# FPGA1_POWER.net
KiCad netlist of a schematic drawn in Altium Designer
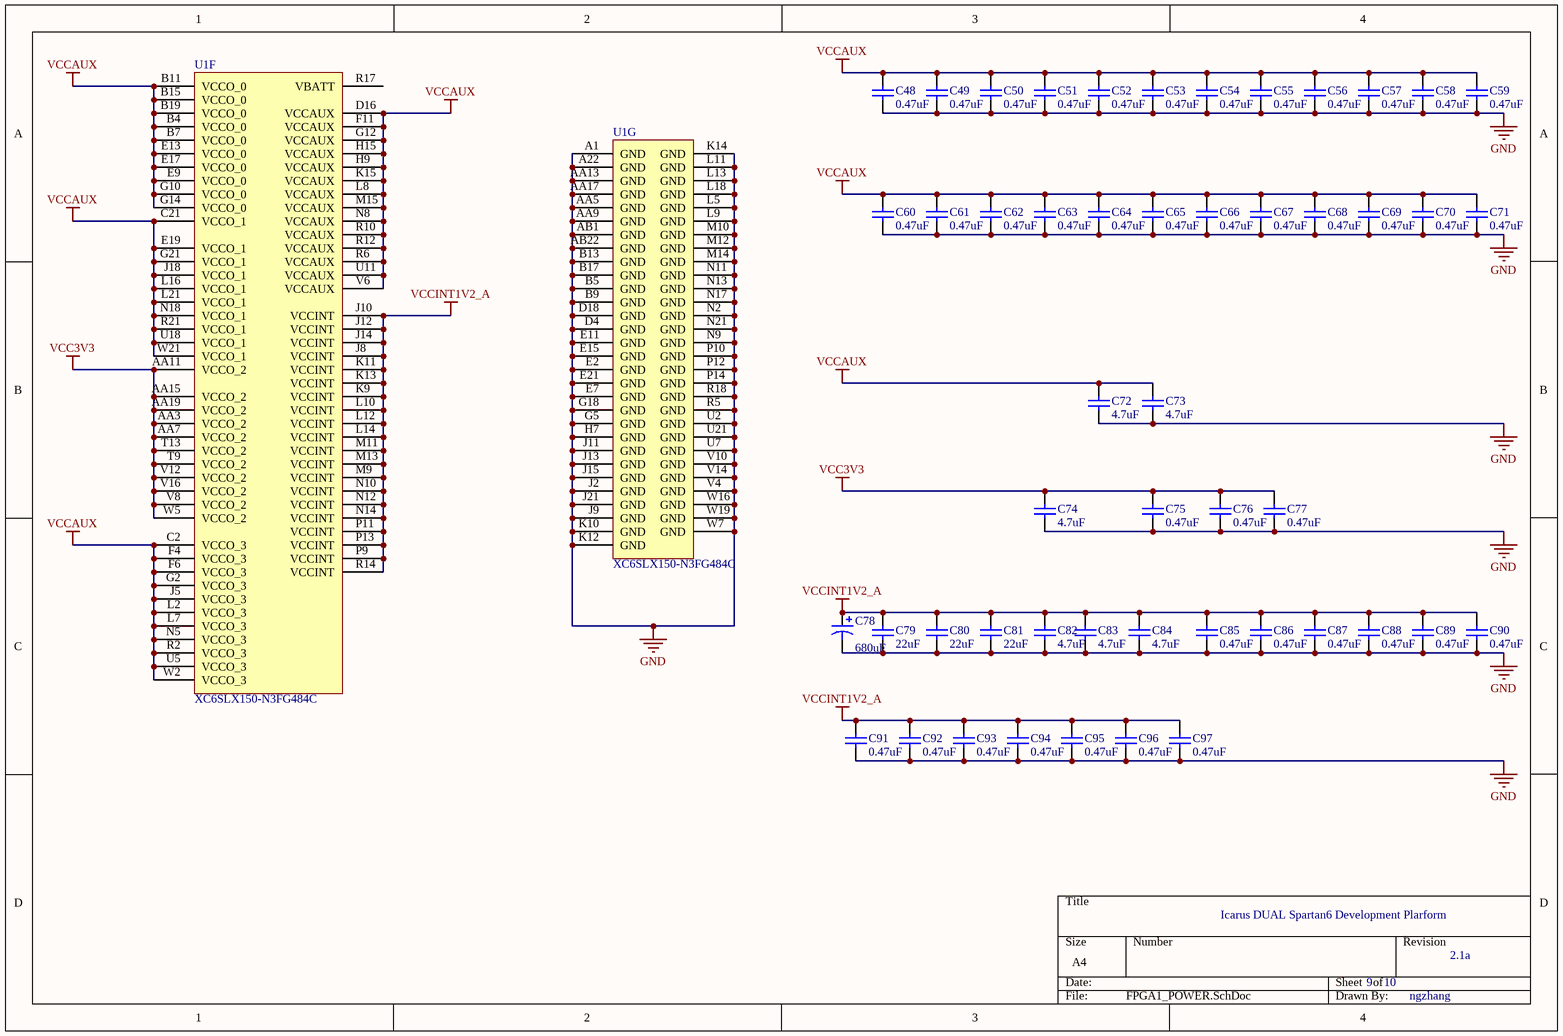
[diagram p0: FPGA1_POWER.SchDoc]

(export (version "E")
  (design (tool "Eeschema 10.0.6"))
  (components
    (comp (ref "C48")
      (value "0.47uF")
      (footprint "0402")
      (description "Capacitor (Semiconductor SIM Model)")
      (fields (field (name "PUBLISHER") "Altium Limited"))
      (libsource (lib "Miscellaneous Devices") (part "Cap Semi"))
    )
    (comp (ref "C49")
      (value "0.47uF")
      (footprint "0402")
      (description "Capacitor (Semiconductor SIM Model)")
      (fields (field (name "PUBLISHER") "Altium Limited"))
      (libsource (lib "Miscellaneous Devices") (part "Cap Semi"))
    )
    (comp (ref "C50")
      (value "0.47uF")
      (footprint "0402")
      (description "Capacitor (Semiconductor SIM Model)")
      (fields (field (name "PUBLISHER") "Altium Limited"))
      (libsource (lib "Miscellaneous Devices") (part "Cap Semi"))
    )
    (comp (ref "C51")
      (value "0.47uF")
      (footprint "0402")
      (description "Capacitor (Semiconductor SIM Model)")
      (fields (field (name "PUBLISHER") "Altium Limited"))
      (libsource (lib "Miscellaneous Devices") (part "Cap Semi"))
    )
    (comp (ref "C52")
      (value "0.47uF")
      (footprint "0402")
      (description "Capacitor (Semiconductor SIM Model)")
      (fields (field (name "PUBLISHER") "Altium Limited"))
      (libsource (lib "Miscellaneous Devices") (part "Cap Semi"))
    )
    (comp (ref "C53")
      (value "0.47uF")
      (footprint "0402")
      (description "Capacitor (Semiconductor SIM Model)")
      (fields (field (name "PUBLISHER") "Altium Limited"))
      (libsource (lib "Miscellaneous Devices") (part "Cap Semi"))
    )
    (comp (ref "C54")
      (value "0.47uF")
      (footprint "0402")
      (description "Capacitor (Semiconductor SIM Model)")
      (fields (field (name "PUBLISHER") "Altium Limited"))
      (libsource (lib "Miscellaneous Devices") (part "Cap Semi"))
    )
    (comp (ref "C55")
      (value "0.47uF")
      (footprint "0402")
      (description "Capacitor (Semiconductor SIM Model)")
      (fields (field (name "PUBLISHER") "Altium Limited"))
      (libsource (lib "Miscellaneous Devices") (part "Cap Semi"))
    )
    (comp (ref "C56")
      (value "0.47uF")
      (footprint "0402")
      (description "Capacitor (Semiconductor SIM Model)")
      (fields (field (name "PUBLISHER") "Altium Limited"))
      (libsource (lib "Miscellaneous Devices") (part "Cap Semi"))
    )
    (comp (ref "C57")
      (value "0.47uF")
      (footprint "0402")
      (description "Capacitor (Semiconductor SIM Model)")
      (fields (field (name "PUBLISHER") "Altium Limited"))
      (libsource (lib "Miscellaneous Devices") (part "Cap Semi"))
    )
    (comp (ref "C58")
      (value "0.47uF")
      (footprint "0402")
      (description "Capacitor (Semiconductor SIM Model)")
      (fields (field (name "PUBLISHER") "Altium Limited"))
      (libsource (lib "Miscellaneous Devices") (part "Cap Semi"))
    )
    (comp (ref "C59")
      (value "0.47uF")
      (footprint "0402")
      (description "Capacitor (Semiconductor SIM Model)")
      (fields (field (name "PUBLISHER") "Altium Limited"))
      (libsource (lib "Miscellaneous Devices") (part "Cap Semi"))
    )
    (comp (ref "C60")
      (value "0.47uF")
      (footprint "0402")
      (description "Capacitor (Semiconductor SIM Model)")
      (fields (field (name "PUBLISHER") "Altium Limited"))
      (libsource (lib "Miscellaneous Devices") (part "Cap Semi"))
    )
    (comp (ref "C61")
      (value "0.47uF")
      (footprint "0402")
      (description "Capacitor (Semiconductor SIM Model)")
      (fields (field (name "PUBLISHER") "Altium Limited"))
      (libsource (lib "Miscellaneous Devices") (part "Cap Semi"))
    )
    (comp (ref "C62")
      (value "0.47uF")
      (footprint "0402")
      (description "Capacitor (Semiconductor SIM Model)")
      (fields (field (name "PUBLISHER") "Altium Limited"))
      (libsource (lib "Miscellaneous Devices") (part "Cap Semi"))
    )
    (comp (ref "C63")
      (value "0.47uF")
      (footprint "0402")
      (description "Capacitor (Semiconductor SIM Model)")
      (fields (field (name "PUBLISHER") "Altium Limited"))
      (libsource (lib "Miscellaneous Devices") (part "Cap Semi"))
    )
    (comp (ref "C64")
      (value "0.47uF")
      (footprint "0402")
      (description "Capacitor (Semiconductor SIM Model)")
      (fields (field (name "PUBLISHER") "Altium Limited"))
      (libsource (lib "Miscellaneous Devices") (part "Cap Semi"))
    )
    (comp (ref "C65")
      (value "0.47uF")
      (footprint "0402")
      (description "Capacitor (Semiconductor SIM Model)")
      (fields (field (name "PUBLISHER") "Altium Limited"))
      (libsource (lib "Miscellaneous Devices") (part "Cap Semi"))
    )
    (comp (ref "C66")
      (value "0.47uF")
      (footprint "0402")
      (description "Capacitor (Semiconductor SIM Model)")
      (fields (field (name "PUBLISHER") "Altium Limited"))
      (libsource (lib "Miscellaneous Devices") (part "Cap Semi"))
    )
    (comp (ref "C67")
      (value "0.47uF")
      (footprint "0402")
      (description "Capacitor (Semiconductor SIM Model)")
      (fields (field (name "PUBLISHER") "Altium Limited"))
      (libsource (lib "Miscellaneous Devices") (part "Cap Semi"))
    )
    (comp (ref "C68")
      (value "0.47uF")
      (footprint "0402")
      (description "Capacitor (Semiconductor SIM Model)")
      (fields (field (name "PUBLISHER") "Altium Limited"))
      (libsource (lib "Miscellaneous Devices") (part "Cap Semi"))
    )
    (comp (ref "C69")
      (value "0.47uF")
      (footprint "0402")
      (description "Capacitor (Semiconductor SIM Model)")
      (fields (field (name "PUBLISHER") "Altium Limited"))
      (libsource (lib "Miscellaneous Devices") (part "Cap Semi"))
    )
    (comp (ref "C70")
      (value "0.47uF")
      (footprint "0402")
      (description "Capacitor (Semiconductor SIM Model)")
      (fields (field (name "PUBLISHER") "Altium Limited"))
      (libsource (lib "Miscellaneous Devices") (part "Cap Semi"))
    )
    (comp (ref "C71")
      (value "0.47uF")
      (footprint "0402")
      (description "Capacitor (Semiconductor SIM Model)")
      (fields (field (name "PUBLISHER") "Altium Limited"))
      (libsource (lib "Miscellaneous Devices") (part "Cap Semi"))
    )
    (comp (ref "C72")
      (value "4.7uF")
      (footprint "C0805")
      (description "Capacitor (Semiconductor SIM Model)")
      (fields (field (name "PUBLISHER") "Altium Limited"))
      (libsource (lib "Miscellaneous Devices") (part "Cap Semi"))
    )
    (comp (ref "C73")
      (value "4.7uF")
      (footprint "C0805")
      (description "Capacitor (Semiconductor SIM Model)")
      (fields (field (name "PUBLISHER") "Altium Limited"))
      (libsource (lib "Miscellaneous Devices") (part "Cap Semi"))
    )
    (comp (ref "C74")
      (value "4.7uF")
      (footprint "C0805")
      (description "Capacitor (Semiconductor SIM Model)")
      (fields (field (name "PUBLISHER") "Altium Limited"))
      (libsource (lib "Miscellaneous Devices") (part "Cap Semi"))
    )
    (comp (ref "C75")
      (value "0.47uF")
      (footprint "0402")
      (description "Capacitor (Semiconductor SIM Model)")
      (fields (field (name "PUBLISHER") "Altium Limited"))
      (libsource (lib "Miscellaneous Devices") (part "Cap Semi"))
    )
    (comp (ref "C76")
      (value "0.47uF")
      (footprint "0402")
      (description "Capacitor (Semiconductor SIM Model)")
      (fields (field (name "PUBLISHER") "Altium Limited"))
      (libsource (lib "Miscellaneous Devices") (part "Cap Semi"))
    )
    (comp (ref "C77")
      (value "0.47uF")
      (footprint "0402")
      (description "Capacitor (Semiconductor SIM Model)")
      (fields (field (name "PUBLISHER") "Altium Limited"))
      (libsource (lib "Miscellaneous Devices") (part "Cap Semi"))
    )
    (comp (ref "C78")
      (value "680uF")
      (footprint "D")
      (description "Polarized Capacitor (Surface Mount)")
      (fields (field (name "PUBLISHER") "Altium Limited"))
      (libsource (lib "Miscellaneous Devices") (part "Cap Pol3"))
    )
    (comp (ref "C79")
      (value "22uF")
      (footprint "C1206")
      (description "Capacitor (Semiconductor SIM Model)")
      (fields (field (name "PUBLISHER") "Altium Limited"))
      (libsource (lib "Miscellaneous Devices") (part "Cap Semi"))
    )
    (comp (ref "C80")
      (value "22uF")
      (footprint "C1206")
      (description "Capacitor (Semiconductor SIM Model)")
      (fields (field (name "PUBLISHER") "Altium Limited"))
      (libsource (lib "Miscellaneous Devices") (part "Cap Semi"))
    )
    (comp (ref "C81")
      (value "22uF")
      (footprint "C1206")
      (description "Capacitor (Semiconductor SIM Model)")
      (fields (field (name "PUBLISHER") "Altium Limited"))
      (libsource (lib "Miscellaneous Devices") (part "Cap Semi"))
    )
    (comp (ref "C82")
      (value "4.7uF")
      (footprint "C0805")
      (description "Capacitor (Semiconductor SIM Model)")
      (fields (field (name "PUBLISHER") "Altium Limited"))
      (libsource (lib "Miscellaneous Devices") (part "Cap Semi"))
    )
    (comp (ref "C83")
      (value "4.7uF")
      (footprint "C0805")
      (description "Capacitor (Semiconductor SIM Model)")
      (fields (field (name "PUBLISHER") "Altium Limited"))
      (libsource (lib "Miscellaneous Devices") (part "Cap Semi"))
    )
    (comp (ref "C84")
      (value "4.7uF")
      (footprint "C0805")
      (description "Capacitor (Semiconductor SIM Model)")
      (fields (field (name "PUBLISHER") "Altium Limited"))
      (libsource (lib "Miscellaneous Devices") (part "Cap Semi"))
    )
    (comp (ref "C85")
      (value "0.47uF")
      (footprint "0402")
      (description "Capacitor (Semiconductor SIM Model)")
      (fields (field (name "PUBLISHER") "Altium Limited"))
      (libsource (lib "Miscellaneous Devices") (part "Cap Semi"))
    )
    (comp (ref "C86")
      (value "0.47uF")
      (footprint "0402")
      (description "Capacitor (Semiconductor SIM Model)")
      (fields (field (name "PUBLISHER") "Altium Limited"))
      (libsource (lib "Miscellaneous Devices") (part "Cap Semi"))
    )
    (comp (ref "C87")
      (value "0.47uF")
      (footprint "0402")
      (description "Capacitor (Semiconductor SIM Model)")
      (fields (field (name "PUBLISHER") "Altium Limited"))
      (libsource (lib "Miscellaneous Devices") (part "Cap Semi"))
    )
    (comp (ref "C88")
      (value "0.47uF")
      (footprint "0402")
      (description "Capacitor (Semiconductor SIM Model)")
      (fields (field (name "PUBLISHER") "Altium Limited"))
      (libsource (lib "Miscellaneous Devices") (part "Cap Semi"))
    )
    (comp (ref "C89")
      (value "0.47uF")
      (footprint "0402")
      (description "Capacitor (Semiconductor SIM Model)")
      (fields (field (name "PUBLISHER") "Altium Limited"))
      (libsource (lib "Miscellaneous Devices") (part "Cap Semi"))
    )
    (comp (ref "C90")
      (value "0.47uF")
      (footprint "0402")
      (description "Capacitor (Semiconductor SIM Model)")
      (fields (field (name "PUBLISHER") "Altium Limited"))
      (libsource (lib "Miscellaneous Devices") (part "Cap Semi"))
    )
    (comp (ref "C91")
      (value "0.47uF")
      (footprint "0402")
      (description "Capacitor (Semiconductor SIM Model)")
      (fields (field (name "PUBLISHER") "Altium Limited"))
      (libsource (lib "Miscellaneous Devices") (part "Cap Semi"))
    )
    (comp (ref "C92")
      (value "0.47uF")
      (footprint "0402")
      (description "Capacitor (Semiconductor SIM Model)")
      (fields (field (name "PUBLISHER") "Altium Limited"))
      (libsource (lib "Miscellaneous Devices") (part "Cap Semi"))
    )
    (comp (ref "C93")
      (value "0.47uF")
      (footprint "0402")
      (description "Capacitor (Semiconductor SIM Model)")
      (fields (field (name "PUBLISHER") "Altium Limited"))
      (libsource (lib "Miscellaneous Devices") (part "Cap Semi"))
    )
    (comp (ref "C94")
      (value "0.47uF")
      (footprint "0402")
      (description "Capacitor (Semiconductor SIM Model)")
      (fields (field (name "PUBLISHER") "Altium Limited"))
      (libsource (lib "Miscellaneous Devices") (part "Cap Semi"))
    )
    (comp (ref "C95")
      (value "0.47uF")
      (footprint "0402")
      (description "Capacitor (Semiconductor SIM Model)")
      (fields (field (name "PUBLISHER") "Altium Limited"))
      (libsource (lib "Miscellaneous Devices") (part "Cap Semi"))
    )
    (comp (ref "C96")
      (value "0.47uF")
      (footprint "0402")
      (description "Capacitor (Semiconductor SIM Model)")
      (fields (field (name "PUBLISHER") "Altium Limited"))
      (libsource (lib "Miscellaneous Devices") (part "Cap Semi"))
    )
    (comp (ref "C97")
      (value "0.47uF")
      (footprint "0402")
      (description "Capacitor (Semiconductor SIM Model)")
      (fields (field (name "PUBLISHER") "Altium Limited"))
      (libsource (lib "Miscellaneous Devices") (part "Cap Semi"))
    )
    (comp (ref "U1")
      (value "XC6SLX150-N3FG484C")
      (footprint "FG484")
      (fields (field (name "PUBLISHER") "Altium Limited"))
      (libsource (lib "Xilinx Spartan-6") (part "XC6SLX150-N3FG484C"))
    )
  )
  (nets
    (net (code "1") (name "GND") (class "Default")
      (node (ref "C48") (pin "1") (pinfunction "1_1") (pintype "passive"))
      (node (ref "C49") (pin "1") (pinfunction "1_1") (pintype "passive"))
      (node (ref "C50") (pin "1") (pinfunction "1_1") (pintype "passive"))
      (node (ref "C51") (pin "1") (pinfunction "1_1") (pintype "passive"))
      (node (ref "C52") (pin "1") (pinfunction "1_1") (pintype "passive"))
      (node (ref "C53") (pin "1") (pinfunction "1_1") (pintype "passive"))
      (node (ref "C54") (pin "1") (pinfunction "1_1") (pintype "passive"))
      (node (ref "C55") (pin "1") (pinfunction "1_1") (pintype "passive"))
      (node (ref "C56") (pin "1") (pinfunction "1_1") (pintype "passive"))
      (node (ref "C57") (pin "1") (pinfunction "1_1") (pintype "passive"))
      (node (ref "C58") (pin "1") (pinfunction "1_1") (pintype "passive"))
      (node (ref "C59") (pin "1") (pinfunction "1_1") (pintype "passive"))
      (node (ref "C60") (pin "1") (pinfunction "1_1") (pintype "passive"))
      (node (ref "C61") (pin "1") (pinfunction "1_1") (pintype "passive"))
      (node (ref "C62") (pin "1") (pinfunction "1_1") (pintype "passive"))
      (node (ref "C63") (pin "1") (pinfunction "1_1") (pintype "passive"))
      (node (ref "C64") (pin "1") (pinfunction "1_1") (pintype "passive"))
      (node (ref "C65") (pin "1") (pinfunction "1_1") (pintype "passive"))
      (node (ref "C66") (pin "1") (pinfunction "1_1") (pintype "passive"))
      (node (ref "C67") (pin "1") (pinfunction "1_1") (pintype "passive"))
      (node (ref "C68") (pin "1") (pinfunction "1_1") (pintype "passive"))
      (node (ref "C69") (pin "1") (pinfunction "1_1") (pintype "passive"))
      (node (ref "C70") (pin "1") (pinfunction "1_1") (pintype "passive"))
      (node (ref "C71") (pin "1") (pinfunction "1_1") (pintype "passive"))
      (node (ref "C72") (pin "1") (pinfunction "1_1") (pintype "passive"))
      (node (ref "C73") (pin "1") (pinfunction "1_1") (pintype "passive"))
      (node (ref "C74") (pin "1") (pinfunction "1_1") (pintype "passive"))
      (node (ref "C75") (pin "1") (pinfunction "1_1") (pintype "passive"))
      (node (ref "C76") (pin "1") (pinfunction "1_1") (pintype "passive"))
      (node (ref "C77") (pin "1") (pinfunction "1_1") (pintype "passive"))
      (node (ref "C78") (pin "2") (pinfunction "2_2") (pintype "passive"))
      (node (ref "C79") (pin "1") (pinfunction "1_1") (pintype "passive"))
      (node (ref "C80") (pin "1") (pinfunction "1_1") (pintype "passive"))
      (node (ref "C81") (pin "1") (pinfunction "1_1") (pintype "passive"))
      (node (ref "C82") (pin "1") (pinfunction "1_1") (pintype "passive"))
      (node (ref "C83") (pin "1") (pinfunction "1_1") (pintype "passive"))
      (node (ref "C84") (pin "1") (pinfunction "1_1") (pintype "passive"))
      (node (ref "C85") (pin "1") (pinfunction "1_1") (pintype "passive"))
      (node (ref "C86") (pin "1") (pinfunction "1_1") (pintype "passive"))
      (node (ref "C87") (pin "1") (pinfunction "1_1") (pintype "passive"))
      (node (ref "C88") (pin "1") (pinfunction "1_1") (pintype "passive"))
      (node (ref "C89") (pin "1") (pinfunction "1_1") (pintype "passive"))
      (node (ref "C90") (pin "1") (pinfunction "1_1") (pintype "passive"))
      (node (ref "C91") (pin "1") (pinfunction "1_1") (pintype "passive"))
      (node (ref "C92") (pin "1") (pinfunction "1_1") (pintype "passive"))
      (node (ref "C93") (pin "1") (pinfunction "1_1") (pintype "passive"))
      (node (ref "C94") (pin "1") (pinfunction "1_1") (pintype "passive"))
      (node (ref "C95") (pin "1") (pinfunction "1_1") (pintype "passive"))
      (node (ref "C96") (pin "1") (pinfunction "1_1") (pintype "passive"))
      (node (ref "C97") (pin "1") (pinfunction "1_1") (pintype "passive"))
      (node (ref "U1") (pin "A1") (pinfunction "GND_A1") (pintype "power_in"))
      (node (ref "U1") (pin "A22") (pinfunction "GND_A22") (pintype "power_in"))
      (node (ref "U1") (pin "AA13") (pinfunction "GND_AA13") (pintype "power_in"))
      (node (ref "U1") (pin "AA17") (pinfunction "GND_AA17") (pintype "power_in"))
      (node (ref "U1") (pin "AA5") (pinfunction "GND_AA5") (pintype "power_in"))
      (node (ref "U1") (pin "AA9") (pinfunction "GND_AA9") (pintype "power_in"))
      (node (ref "U1") (pin "AB1") (pinfunction "GND_AB1") (pintype "power_in"))
      (node (ref "U1") (pin "AB22") (pinfunction "GND_AB22") (pintype "power_in"))
      (node (ref "U1") (pin "B13") (pinfunction "GND_B13") (pintype "power_in"))
      (node (ref "U1") (pin "B17") (pinfunction "GND_B17") (pintype "power_in"))
      (node (ref "U1") (pin "B5") (pinfunction "GND_B5") (pintype "power_in"))
      (node (ref "U1") (pin "B9") (pinfunction "GND_B9") (pintype "power_in"))
      (node (ref "U1") (pin "D18") (pinfunction "GND_D18") (pintype "power_in"))
      (node (ref "U1") (pin "D4") (pinfunction "GND_D4") (pintype "power_in"))
      (node (ref "U1") (pin "E11") (pinfunction "GND_E11") (pintype "power_in"))
      (node (ref "U1") (pin "E15") (pinfunction "GND_E15") (pintype "power_in"))
      (node (ref "U1") (pin "E2") (pinfunction "GND_E2") (pintype "power_in"))
      (node (ref "U1") (pin "E21") (pinfunction "GND_E21") (pintype "power_in"))
      (node (ref "U1") (pin "E7") (pinfunction "GND_E7") (pintype "power_in"))
      (node (ref "U1") (pin "G18") (pinfunction "GND_G18") (pintype "power_in"))
      (node (ref "U1") (pin "G5") (pinfunction "GND_G5") (pintype "power_in"))
      (node (ref "U1") (pin "H7") (pinfunction "GND_H7") (pintype "power_in"))
      (node (ref "U1") (pin "J11") (pinfunction "GND_J11") (pintype "power_in"))
      (node (ref "U1") (pin "J13") (pinfunction "GND_J13") (pintype "power_in"))
      (node (ref "U1") (pin "J15") (pinfunction "GND_J15") (pintype "power_in"))
      (node (ref "U1") (pin "J2") (pinfunction "GND_J2") (pintype "power_in"))
      (node (ref "U1") (pin "J21") (pinfunction "GND_J21") (pintype "power_in"))
      (node (ref "U1") (pin "J9") (pinfunction "GND_J9") (pintype "power_in"))
      (node (ref "U1") (pin "K10") (pinfunction "GND_K10") (pintype "power_in"))
      (node (ref "U1") (pin "K12") (pinfunction "GND_K12") (pintype "power_in"))
      (node (ref "U1") (pin "K14") (pinfunction "GND_K14") (pintype "power_in"))
      (node (ref "U1") (pin "L11") (pinfunction "GND_L11") (pintype "power_in"))
      (node (ref "U1") (pin "L13") (pinfunction "GND_L13") (pintype "power_in"))
      (node (ref "U1") (pin "L18") (pinfunction "GND_L18") (pintype "power_in"))
      (node (ref "U1") (pin "L5") (pinfunction "GND_L5") (pintype "power_in"))
      (node (ref "U1") (pin "L9") (pinfunction "GND_L9") (pintype "power_in"))
      (node (ref "U1") (pin "M10") (pinfunction "GND_M10") (pintype "power_in"))
      (node (ref "U1") (pin "M12") (pinfunction "GND_M12") (pintype "power_in"))
      (node (ref "U1") (pin "M14") (pinfunction "GND_M14") (pintype "power_in"))
      (node (ref "U1") (pin "N11") (pinfunction "GND_N11") (pintype "power_in"))
      (node (ref "U1") (pin "N13") (pinfunction "GND_N13") (pintype "power_in"))
      (node (ref "U1") (pin "N17") (pinfunction "GND_N17") (pintype "power_in"))
      (node (ref "U1") (pin "N2") (pinfunction "GND_N2") (pintype "power_in"))
      (node (ref "U1") (pin "N21") (pinfunction "GND_N21") (pintype "power_in"))
      (node (ref "U1") (pin "N9") (pinfunction "GND_N9") (pintype "power_in"))
      (node (ref "U1") (pin "P10") (pinfunction "GND_P10") (pintype "power_in"))
      (node (ref "U1") (pin "P12") (pinfunction "GND_P12") (pintype "power_in"))
      (node (ref "U1") (pin "P14") (pinfunction "GND_P14") (pintype "power_in"))
      (node (ref "U1") (pin "R18") (pinfunction "GND_R18") (pintype "power_in"))
      (node (ref "U1") (pin "R5") (pinfunction "GND_R5") (pintype "power_in"))
      (node (ref "U1") (pin "U2") (pinfunction "GND_U2") (pintype "power_in"))
      (node (ref "U1") (pin "U21") (pinfunction "GND_U21") (pintype "power_in"))
      (node (ref "U1") (pin "U7") (pinfunction "GND_U7") (pintype "power_in"))
      (node (ref "U1") (pin "V10") (pinfunction "GND_V10") (pintype "power_in"))
      (node (ref "U1") (pin "V14") (pinfunction "GND_V14") (pintype "power_in"))
      (node (ref "U1") (pin "V4") (pinfunction "GND_V4") (pintype "power_in"))
      (node (ref "U1") (pin "W16") (pinfunction "GND_W16") (pintype "power_in"))
      (node (ref "U1") (pin "W19") (pinfunction "GND_W19") (pintype "power_in"))
      (node (ref "U1") (pin "W7") (pinfunction "GND_W7") (pintype "power_in"))
    )
    (net (code "2") (name "VCC3V3") (class "Default")
      (node (ref "C74") (pin "2") (pinfunction "2_2") (pintype "passive"))
      (node (ref "C75") (pin "2") (pinfunction "2_2") (pintype "passive"))
      (node (ref "C76") (pin "2") (pinfunction "2_2") (pintype "passive"))
      (node (ref "C77") (pin "2") (pinfunction "2_2") (pintype "passive"))
      (node (ref "U1") (pin "AA11") (pinfunction "VCCO_2_AA11") (pintype "power_in"))
      (node (ref "U1") (pin "AA15") (pinfunction "VCCO_2_AA15") (pintype "power_in"))
      (node (ref "U1") (pin "AA19") (pinfunction "VCCO_2_AA19") (pintype "power_in"))
      (node (ref "U1") (pin "AA3") (pinfunction "VCCO_2_AA3") (pintype "power_in"))
      (node (ref "U1") (pin "AA7") (pinfunction "VCCO_2_AA7") (pintype "power_in"))
      (node (ref "U1") (pin "T13") (pinfunction "VCCO_2_T13") (pintype "power_in"))
      (node (ref "U1") (pin "T9") (pinfunction "VCCO_2_T9") (pintype "power_in"))
      (node (ref "U1") (pin "V12") (pinfunction "VCCO_2_V12") (pintype "power_in"))
      (node (ref "U1") (pin "V16") (pinfunction "VCCO_2_V16") (pintype "power_in"))
      (node (ref "U1") (pin "V8") (pinfunction "VCCO_2_V8") (pintype "power_in"))
      (node (ref "U1") (pin "W5") (pinfunction "VCCO_2_W5") (pintype "power_in"))
    )
    (net (code "3") (name "VCCAUX") (class "Default")
      (node (ref "C48") (pin "2") (pinfunction "2_2") (pintype "passive"))
      (node (ref "C49") (pin "2") (pinfunction "2_2") (pintype "passive"))
      (node (ref "C50") (pin "2") (pinfunction "2_2") (pintype "passive"))
      (node (ref "C51") (pin "2") (pinfunction "2_2") (pintype "passive"))
      (node (ref "C52") (pin "2") (pinfunction "2_2") (pintype "passive"))
      (node (ref "C53") (pin "2") (pinfunction "2_2") (pintype "passive"))
      (node (ref "C54") (pin "2") (pinfunction "2_2") (pintype "passive"))
      (node (ref "C55") (pin "2") (pinfunction "2_2") (pintype "passive"))
      (node (ref "C56") (pin "2") (pinfunction "2_2") (pintype "passive"))
      (node (ref "C57") (pin "2") (pinfunction "2_2") (pintype "passive"))
      (node (ref "C58") (pin "2") (pinfunction "2_2") (pintype "passive"))
      (node (ref "C59") (pin "2") (pinfunction "2_2") (pintype "passive"))
      (node (ref "C60") (pin "2") (pinfunction "2_2") (pintype "passive"))
      (node (ref "C61") (pin "2") (pinfunction "2_2") (pintype "passive"))
      (node (ref "C62") (pin "2") (pinfunction "2_2") (pintype "passive"))
      (node (ref "C63") (pin "2") (pinfunction "2_2") (pintype "passive"))
      (node (ref "C64") (pin "2") (pinfunction "2_2") (pintype "passive"))
      (node (ref "C65") (pin "2") (pinfunction "2_2") (pintype "passive"))
      (node (ref "C66") (pin "2") (pinfunction "2_2") (pintype "passive"))
      (node (ref "C67") (pin "2") (pinfunction "2_2") (pintype "passive"))
      (node (ref "C68") (pin "2") (pinfunction "2_2") (pintype "passive"))
      (node (ref "C69") (pin "2") (pinfunction "2_2") (pintype "passive"))
      (node (ref "C70") (pin "2") (pinfunction "2_2") (pintype "passive"))
      (node (ref "C71") (pin "2") (pinfunction "2_2") (pintype "passive"))
      (node (ref "C72") (pin "2") (pinfunction "2_2") (pintype "passive"))
      (node (ref "C73") (pin "2") (pinfunction "2_2") (pintype "passive"))
      (node (ref "U1") (pin "B11") (pinfunction "VCCO_0_B11") (pintype "power_in"))
      (node (ref "U1") (pin "B15") (pinfunction "VCCO_0_B15") (pintype "power_in"))
      (node (ref "U1") (pin "B19") (pinfunction "VCCO_0_B19") (pintype "power_in"))
      (node (ref "U1") (pin "B4") (pinfunction "VCCO_0_B4") (pintype "power_in"))
      (node (ref "U1") (pin "B7") (pinfunction "VCCO_0_B7") (pintype "power_in"))
      (node (ref "U1") (pin "C2") (pinfunction "VCCO_3_C2") (pintype "power_in"))
      (node (ref "U1") (pin "C21") (pinfunction "VCCO_1_C21") (pintype "power_in"))
      (node (ref "U1") (pin "D16") (pinfunction "VCCAUX_D16") (pintype "power_in"))
      (node (ref "U1") (pin "E13") (pinfunction "VCCO_0_E13") (pintype "power_in"))
      (node (ref "U1") (pin "E17") (pinfunction "VCCO_0_E17") (pintype "power_in"))
      (node (ref "U1") (pin "E19") (pinfunction "VCCO_1_E19") (pintype "power_in"))
      (node (ref "U1") (pin "E9") (pinfunction "VCCO_0_E9") (pintype "power_in"))
      (node (ref "U1") (pin "F11") (pinfunction "VCCAUX_F11") (pintype "power_in"))
      (node (ref "U1") (pin "F4") (pinfunction "VCCO_3_F4") (pintype "power_in"))
      (node (ref "U1") (pin "F6") (pinfunction "VCCO_3_F6") (pintype "power_in"))
      (node (ref "U1") (pin "G10") (pinfunction "VCCO_0_G10") (pintype "power_in"))
      (node (ref "U1") (pin "G12") (pinfunction "VCCAUX_G12") (pintype "power_in"))
      (node (ref "U1") (pin "G14") (pinfunction "VCCO_0_G14") (pintype "power_in"))
      (node (ref "U1") (pin "G2") (pinfunction "VCCO_3_G2") (pintype "power_in"))
      (node (ref "U1") (pin "G21") (pinfunction "VCCO_1_G21") (pintype "power_in"))
      (node (ref "U1") (pin "H15") (pinfunction "VCCAUX_H15") (pintype "power_in"))
      (node (ref "U1") (pin "H9") (pinfunction "VCCAUX_H9") (pintype "power_in"))
      (node (ref "U1") (pin "J18") (pinfunction "VCCO_1_J18") (pintype "power_in"))
      (node (ref "U1") (pin "J5") (pinfunction "VCCO_3_J5") (pintype "power_in"))
      (node (ref "U1") (pin "K15") (pinfunction "VCCAUX_K15") (pintype "power_in"))
      (node (ref "U1") (pin "L16") (pinfunction "VCCO_1_L16") (pintype "power_in"))
      (node (ref "U1") (pin "L2") (pinfunction "VCCO_3_L2") (pintype "power_in"))
      (node (ref "U1") (pin "L21") (pinfunction "VCCO_1_L21") (pintype "power_in"))
      (node (ref "U1") (pin "L7") (pinfunction "VCCO_3_L7") (pintype "power_in"))
      (node (ref "U1") (pin "L8") (pinfunction "VCCAUX_L8") (pintype "power_in"))
      (node (ref "U1") (pin "M15") (pinfunction "VCCAUX_M15") (pintype "power_in"))
      (node (ref "U1") (pin "N18") (pinfunction "VCCO_1_N18") (pintype "power_in"))
      (node (ref "U1") (pin "N5") (pinfunction "VCCO_3_N5") (pintype "power_in"))
      (node (ref "U1") (pin "N8") (pinfunction "VCCAUX_N8") (pintype "power_in"))
      (node (ref "U1") (pin "R10") (pinfunction "VCCAUX_R10") (pintype "power_in"))
      (node (ref "U1") (pin "R12") (pinfunction "VCCAUX_R12") (pintype "power_in"))
      (node (ref "U1") (pin "R2") (pinfunction "VCCO_3_R2") (pintype "power_in"))
      (node (ref "U1") (pin "R21") (pinfunction "VCCO_1_R21") (pintype "power_in"))
      (node (ref "U1") (pin "R6") (pinfunction "VCCAUX_R6") (pintype "power_in"))
      (node (ref "U1") (pin "U11") (pinfunction "VCCAUX_U11") (pintype "power_in"))
      (node (ref "U1") (pin "U18") (pinfunction "VCCO_1_U18") (pintype "power_in"))
      (node (ref "U1") (pin "U5") (pinfunction "VCCO_3_U5") (pintype "power_in"))
      (node (ref "U1") (pin "V6") (pinfunction "VCCAUX_V6") (pintype "power_in"))
      (node (ref "U1") (pin "W2") (pinfunction "VCCO_3_W2") (pintype "power_in"))
      (node (ref "U1") (pin "W21") (pinfunction "VCCO_1_W21") (pintype "power_in"))
    )
    (net (code "4") (name "VCCINT1V2_A") (class "Default")
      (node (ref "C78") (pin "1") (pinfunction "1_1") (pintype "passive"))
      (node (ref "C79") (pin "2") (pinfunction "2_2") (pintype "passive"))
      (node (ref "C80") (pin "2") (pinfunction "2_2") (pintype "passive"))
      (node (ref "C81") (pin "2") (pinfunction "2_2") (pintype "passive"))
      (node (ref "C82") (pin "2") (pinfunction "2_2") (pintype "passive"))
      (node (ref "C83") (pin "2") (pinfunction "2_2") (pintype "passive"))
      (node (ref "C84") (pin "2") (pinfunction "2_2") (pintype "passive"))
      (node (ref "C85") (pin "2") (pinfunction "2_2") (pintype "passive"))
      (node (ref "C86") (pin "2") (pinfunction "2_2") (pintype "passive"))
      (node (ref "C87") (pin "2") (pinfunction "2_2") (pintype "passive"))
      (node (ref "C88") (pin "2") (pinfunction "2_2") (pintype "passive"))
      (node (ref "C89") (pin "2") (pinfunction "2_2") (pintype "passive"))
      (node (ref "C90") (pin "2") (pinfunction "2_2") (pintype "passive"))
      (node (ref "C91") (pin "2") (pinfunction "2_2") (pintype "passive"))
      (node (ref "C92") (pin "2") (pinfunction "2_2") (pintype "passive"))
      (node (ref "C93") (pin "2") (pinfunction "2_2") (pintype "passive"))
      (node (ref "C94") (pin "2") (pinfunction "2_2") (pintype "passive"))
      (node (ref "C95") (pin "2") (pinfunction "2_2") (pintype "passive"))
      (node (ref "C96") (pin "2") (pinfunction "2_2") (pintype "passive"))
      (node (ref "C97") (pin "2") (pinfunction "2_2") (pintype "passive"))
      (node (ref "U1") (pin "J10") (pinfunction "VCCINT_J10") (pintype "power_in"))
      (node (ref "U1") (pin "J12") (pinfunction "VCCINT_J12") (pintype "power_in"))
      (node (ref "U1") (pin "J14") (pinfunction "VCCINT_J14") (pintype "power_in"))
      (node (ref "U1") (pin "J8") (pinfunction "VCCINT_J8") (pintype "power_in"))
      (node (ref "U1") (pin "K11") (pinfunction "VCCINT_K11") (pintype "power_in"))
      (node (ref "U1") (pin "K13") (pinfunction "VCCINT_K13") (pintype "power_in"))
      (node (ref "U1") (pin "K9") (pinfunction "VCCINT_K9") (pintype "power_in"))
      (node (ref "U1") (pin "L10") (pinfunction "VCCINT_L10") (pintype "power_in"))
      (node (ref "U1") (pin "L12") (pinfunction "VCCINT_L12") (pintype "power_in"))
      (node (ref "U1") (pin "L14") (pinfunction "VCCINT_L14") (pintype "power_in"))
      (node (ref "U1") (pin "M11") (pinfunction "VCCINT_M11") (pintype "power_in"))
      (node (ref "U1") (pin "M13") (pinfunction "VCCINT_M13") (pintype "power_in"))
      (node (ref "U1") (pin "M9") (pinfunction "VCCINT_M9") (pintype "power_in"))
      (node (ref "U1") (pin "N10") (pinfunction "VCCINT_N10") (pintype "power_in"))
      (node (ref "U1") (pin "N12") (pinfunction "VCCINT_N12") (pintype "power_in"))
      (node (ref "U1") (pin "N14") (pinfunction "VCCINT_N14") (pintype "power_in"))
      (node (ref "U1") (pin "P11") (pinfunction "VCCINT_P11") (pintype "power_in"))
      (node (ref "U1") (pin "P13") (pinfunction "VCCINT_P13") (pintype "power_in"))
      (node (ref "U1") (pin "P9") (pinfunction "VCCINT_P9") (pintype "power_in"))
      (node (ref "U1") (pin "R14") (pinfunction "VCCINT_R14") (pintype "power_in"))
    )
    (net (code "5") (name "unconnected-(U1F-VBATT-PadR17)") (class "Default")
      (node (ref "U1") (pin "R17") (pinfunction "VBATT_R17") (pintype "power_in"))
    )
  )
)
